# D5035-01.net
KiCad netlist of a schematic drawn in Altium Designer
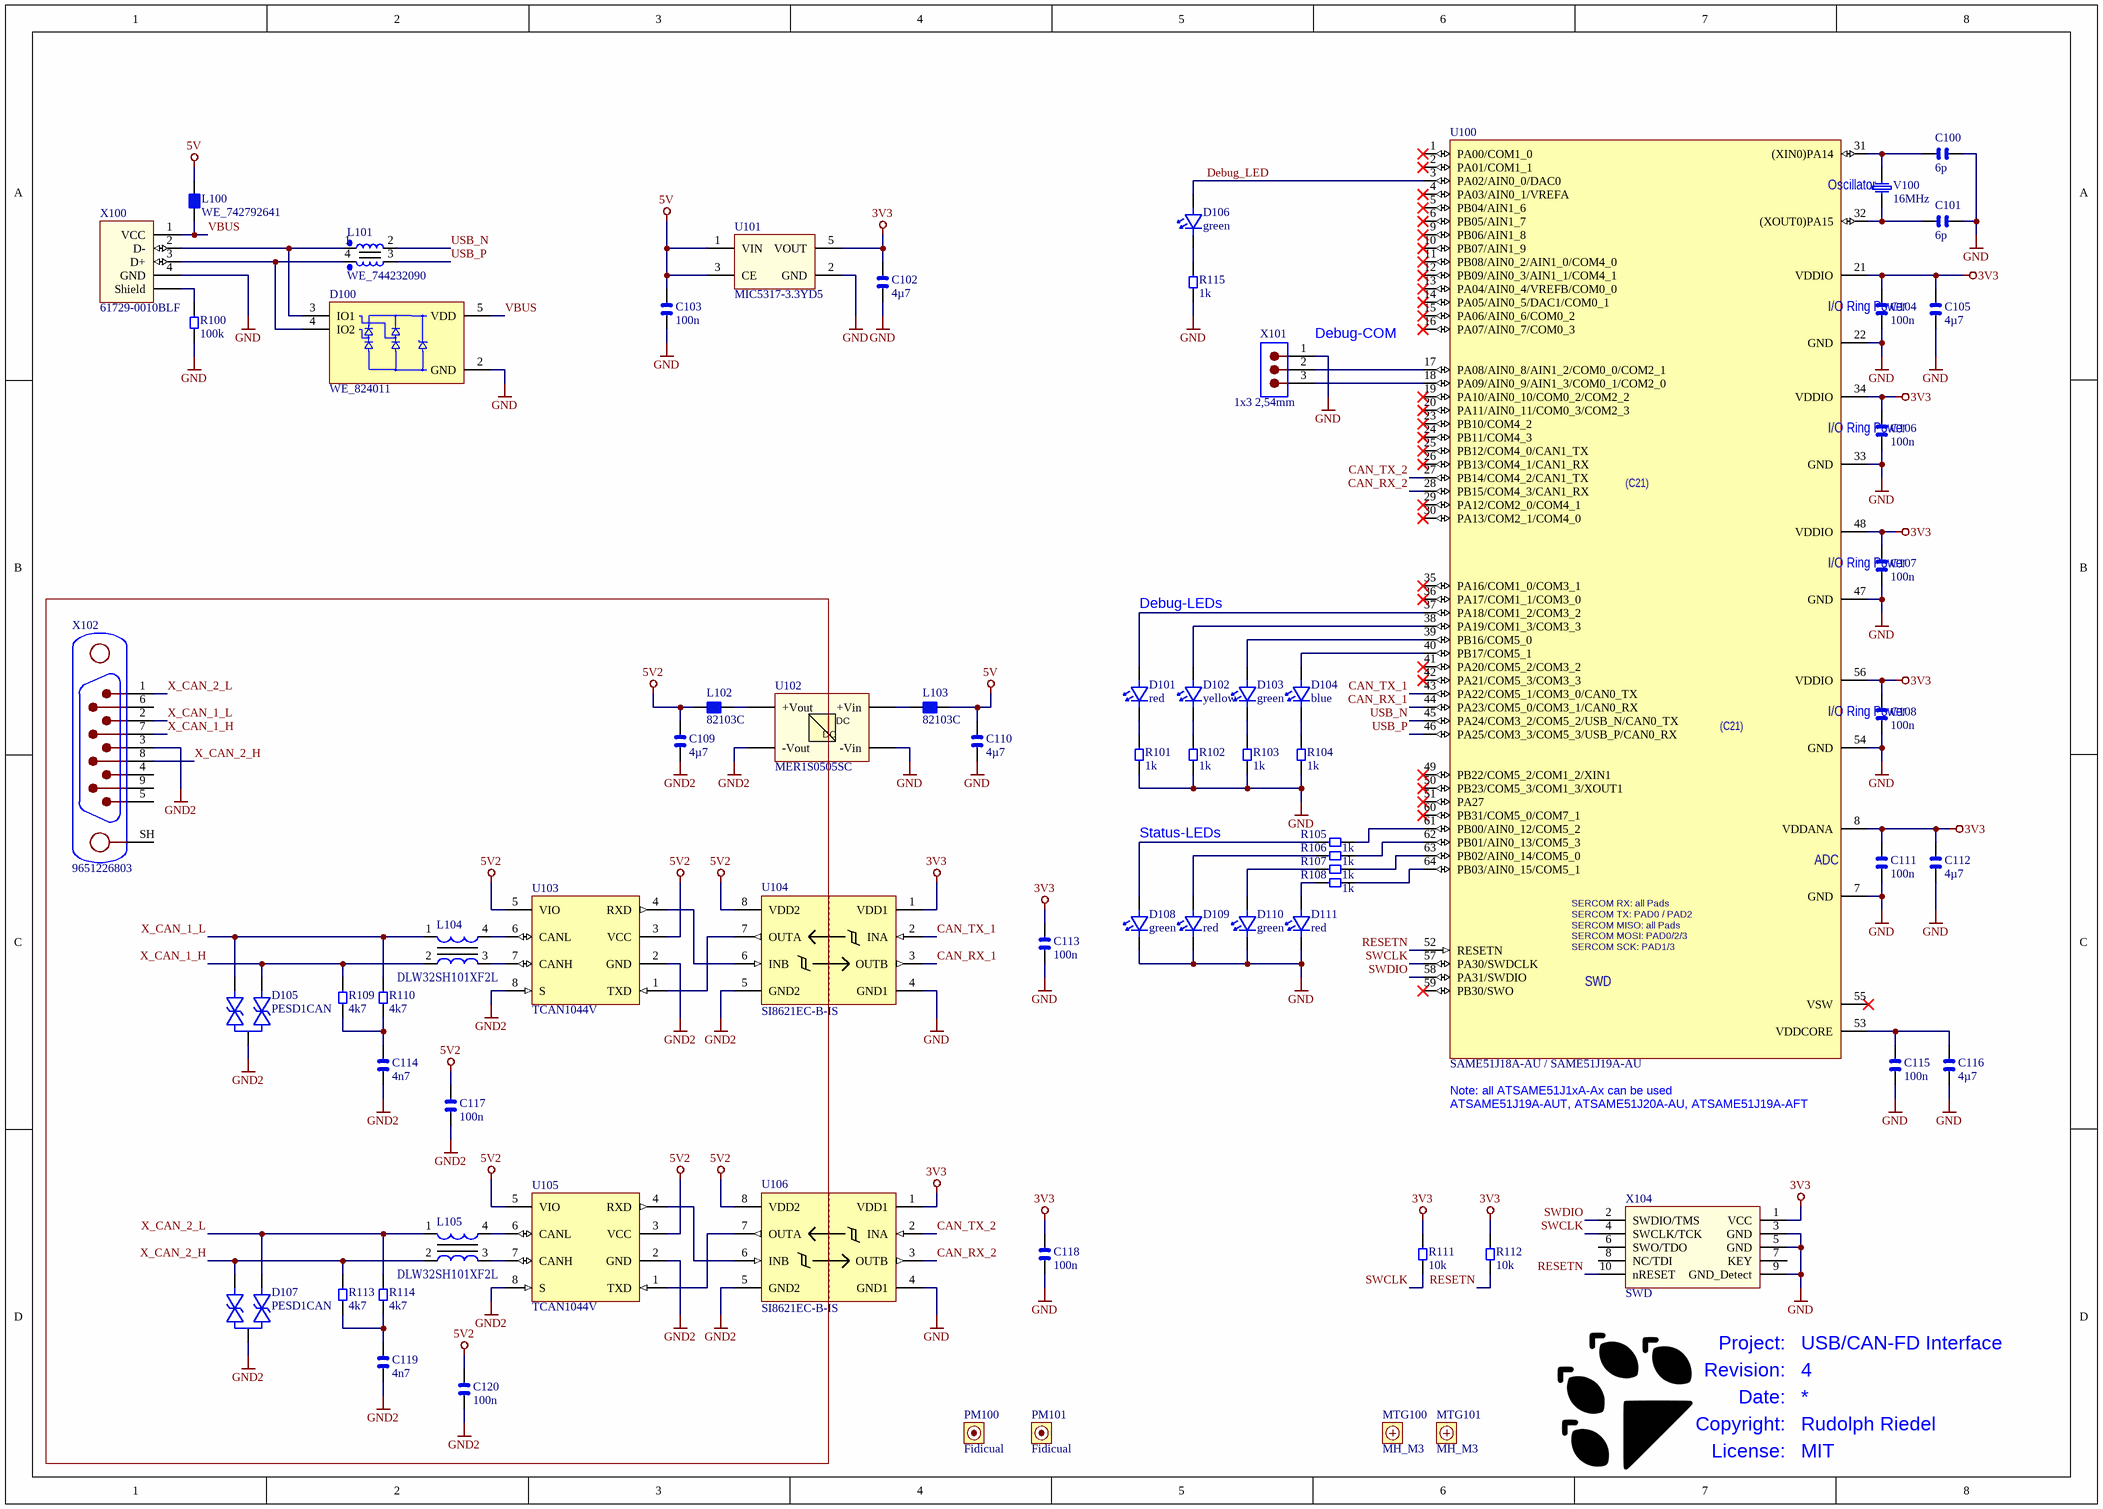
[diagram p0: D5035-01.SchDoc]

(export (version "E")
  (design (tool "Eeschema 10.0.6"))
  (components
    (comp (ref "C100")
      (value "6p")
      (footprint "CAPC1608X09L")
      (description "0603 Chip Capacitor")
      (fields (field (name "PART NUMBER") "CAPC_0603") (field (name "EDITOR") "rriedel"))
      (libsource (lib "HW-Labor_GF") (part "CAP_2_V2"))
    )
    (comp (ref "C101")
      (value "6p")
      (footprint "CAPC1608X09L")
      (description "0603 Chip Capacitor")
      (fields (field (name "PART NUMBER") "CAPC_0603") (field (name "EDITOR") "rriedel"))
      (libsource (lib "HW-Labor_GF") (part "CAP_2_V2"))
    )
    (comp (ref "C102")
      (value "4µ7")
      (footprint "CAPC2012X14L")
      (description "0805 Chip Capacitor")
      (fields (field (name "PART NUMBER") "CAPC_0805") (field (name "EDITOR") "rriedel"))
      (libsource (lib "HW-Labor_GF") (part "CAP_2_V2"))
    )
    (comp (ref "C103")
      (value "100n")
      (footprint "CAPC1608X09L")
      (description "0603 Chip Capacitor")
      (fields (field (name "PART NUMBER") "CAPC_0603") (field (name "EDITOR") "rriedel"))
      (libsource (lib "HW-Labor_GF") (part "CAP_2_V2"))
    )
    (comp (ref "C104")
      (value "100n")
      (footprint "CAPC1608X09L")
      (description "0603 Chip Capacitor")
      (fields (field (name "PART NUMBER") "CAPC_0603") (field (name "EDITOR") "rriedel"))
      (libsource (lib "HW-Labor_GF") (part "CAP_2_V2"))
    )
    (comp (ref "C105")
      (value "4µ7")
      (footprint "CAPC2012X14L")
      (description "0805 Chip Capacitor")
      (fields (field (name "PART NUMBER") "CAPC_0805") (field (name "EDITOR") "rriedel"))
      (libsource (lib "HW-Labor_GF") (part "CAP_2_V2"))
    )
    (comp (ref "C106")
      (value "100n")
      (footprint "CAPC1608X09L")
      (description "0603 Chip Capacitor")
      (fields (field (name "PART NUMBER") "CAPC_0603") (field (name "EDITOR") "rriedel"))
      (libsource (lib "HW-Labor_GF") (part "CAP_2_V2"))
    )
    (comp (ref "C107")
      (value "100n")
      (footprint "CAPC1608X09L")
      (description "0603 Chip Capacitor")
      (fields (field (name "PART NUMBER") "CAPC_0603") (field (name "EDITOR") "rriedel"))
      (libsource (lib "HW-Labor_GF") (part "CAP_2_V2"))
    )
    (comp (ref "C108")
      (value "100n")
      (footprint "CAPC1608X09L")
      (description "0603 Chip Capacitor")
      (fields (field (name "PART NUMBER") "CAPC_0603") (field (name "EDITOR") "rriedel"))
      (libsource (lib "HW-Labor_GF") (part "CAP_2_V2"))
    )
    (comp (ref "C109")
      (value "4µ7")
      (footprint "CAPC2012X14L")
      (description "0805 Chip Capacitor")
      (fields (field (name "PART NUMBER") "CAPC_0805") (field (name "EDITOR") "rriedel"))
      (libsource (lib "HW-Labor_GF") (part "CAP_2_V2"))
    )
    (comp (ref "C110")
      (value "4µ7")
      (footprint "CAPC2012X14L")
      (description "0805 Chip Capacitor")
      (fields (field (name "PART NUMBER") "CAPC_0805") (field (name "EDITOR") "rriedel"))
      (libsource (lib "HW-Labor_GF") (part "CAP_2_V2"))
    )
    (comp (ref "C111")
      (value "100n")
      (footprint "CAPC1608X09L")
      (description "0603 Chip Capacitor")
      (fields (field (name "PART NUMBER") "CAPC_0603") (field (name "EDITOR") "rriedel"))
      (libsource (lib "HW-Labor_GF") (part "CAP_2_V2"))
    )
    (comp (ref "C112")
      (value "4µ7")
      (footprint "CAPC2012X14L")
      (description "0805 Chip Capacitor")
      (fields (field (name "PART NUMBER") "CAPC_0805") (field (name "EDITOR") "rriedel"))
      (libsource (lib "HW-Labor_GF") (part "CAP_2_V2"))
    )
    (comp (ref "C113")
      (value "100n")
      (footprint "CAPC1608X09L")
      (description "0603 Chip Capacitor")
      (fields (field (name "PART NUMBER") "CAPC_0603") (field (name "EDITOR") "rriedel"))
      (libsource (lib "HW-Labor_GF") (part "CAP_2_V2"))
    )
    (comp (ref "C114")
      (value "4n7")
      (footprint "CAPC2012X14L")
      (description "0805 Chip Capacitor")
      (fields (field (name "PART NUMBER") "CAPC_0805") (field (name "EDITOR") "rriedel"))
      (libsource (lib "HW-Labor_GF") (part "CAP_2_V2"))
    )
    (comp (ref "C115")
      (value "100n")
      (footprint "CAPC1608X09L")
      (description "0603 Chip Capacitor")
      (fields (field (name "PART NUMBER") "CAPC_0603") (field (name "EDITOR") "rriedel"))
      (libsource (lib "HW-Labor_GF") (part "CAP_2_V2"))
    )
    (comp (ref "C116")
      (value "4µ7")
      (footprint "CAPC2012X14L")
      (description "0805 Chip Capacitor")
      (fields (field (name "PART NUMBER") "CAPC_0805") (field (name "EDITOR") "rriedel"))
      (libsource (lib "HW-Labor_GF") (part "CAP_2_V2"))
    )
    (comp (ref "C117")
      (value "100n")
      (footprint "CAPC1608X09L")
      (description "0603 Chip Capacitor")
      (fields (field (name "PART NUMBER") "CAPC_0603") (field (name "EDITOR") "rriedel"))
      (libsource (lib "HW-Labor_GF") (part "CAP_2_V2"))
    )
    (comp (ref "C118")
      (value "100n")
      (footprint "CAPC1608X09L")
      (description "0603 Chip Capacitor")
      (fields (field (name "PART NUMBER") "CAPC_0603") (field (name "EDITOR") "rriedel"))
      (libsource (lib "HW-Labor_GF") (part "CAP_2_V2"))
    )
    (comp (ref "C119")
      (value "4n7")
      (footprint "CAPC2012X14L")
      (description "0805 Chip Capacitor")
      (fields (field (name "PART NUMBER") "CAPC_0805") (field (name "EDITOR") "rriedel"))
      (libsource (lib "HW-Labor_GF") (part "CAP_2_V2"))
    )
    (comp (ref "C120")
      (value "100n")
      (footprint "CAPC1608X09L")
      (description "0603 Chip Capacitor")
      (fields (field (name "PART NUMBER") "CAPC_0603") (field (name "EDITOR") "rriedel"))
      (libsource (lib "HW-Labor_GF") (part "CAP_2_V2"))
    )
    (comp (ref "D100")
      (value "WE_824011")
      (footprint "SOT95P280X110-5N")
      (description "TVS Diode Array WE-TVS")
      (fields
        (field (name "MANUFACTURER") "Wuerth")
        (field (name "DISTRIBUTOR_1_PART_NUMBER") "732-4465-1-ND")
        (field (name "EDITOR") "rriedel")
      )
      (libsource (lib "HW-Labor_GF") (part "WE-824011"))
    )
    (comp (ref "D101")
      (value "red")
      (footprint "DIOC1608X06N_LED")
      (description "LED, 0603")
      (fields (field (name "PART NUMBER") "LED_0603") (field (name "EDITOR") "rriedel"))
      (libsource (lib "HW-Labor_GF") (part "LED_generic"))
    )
    (comp (ref "D102")
      (value "yellow")
      (footprint "DIOC1608X06N_LED")
      (description "LED, 0603")
      (fields (field (name "PART NUMBER") "LED_0603") (field (name "EDITOR") "rriedel"))
      (libsource (lib "HW-Labor_GF") (part "LED_generic"))
    )
    (comp (ref "D103")
      (value "green")
      (footprint "DIOC1608X06N_LED")
      (description "LED, 0603")
      (fields (field (name "PART NUMBER") "LED_0603") (field (name "EDITOR") "rriedel"))
      (libsource (lib "HW-Labor_GF") (part "LED_generic"))
    )
    (comp (ref "D104")
      (value "blue")
      (footprint "DIOC1608X06N_LED")
      (description "LED, 0603")
      (fields (field (name "PART NUMBER") "LED_0603") (field (name "EDITOR") "rriedel"))
      (libsource (lib "HW-Labor_GF") (part "LED_generic"))
    )
    (comp (ref "D105")
      (value "PESD1CAN")
      (footprint "SOT95P280X110-3N")
      (description "CAN bus ESD protection diode")
      (fields
        (field (name "MANUFACTURER") "Nexperia")
        (field (name "DISTRIBUTOR_1_PART_NUMBER") "1727-3817-1-ND")
        (field (name "EDITOR") "rriedel")
      )
      (libsource (lib "HW-Labor_GF") (part "PESD1CAN"))
    )
    (comp (ref "D106")
      (value "green")
      (footprint "DIOC1608X06N_LED")
      (description "LED, 0603")
      (fields (field (name "PART NUMBER") "LED_0603") (field (name "EDITOR") "rriedel"))
      (libsource (lib "HW-Labor_GF") (part "LED_generic"))
    )
    (comp (ref "D107")
      (value "PESD1CAN")
      (footprint "SOT95P280X110-3N")
      (description "CAN bus ESD protection diode")
      (fields
        (field (name "MANUFACTURER") "Nexperia")
        (field (name "DISTRIBUTOR_1_PART_NUMBER") "1727-3817-1-ND")
        (field (name "EDITOR") "rriedel")
      )
      (libsource (lib "HW-Labor_GF") (part "PESD1CAN"))
    )
    (comp (ref "D108")
      (value "green")
      (footprint "DIOC1608X06N_LED")
      (description "LED, 0603")
      (fields (field (name "PART NUMBER") "LED_0603") (field (name "EDITOR") "rriedel"))
      (libsource (lib "HW-Labor_GF") (part "LED_generic"))
    )
    (comp (ref "D109")
      (value "red")
      (footprint "DIOC1608X06N_LED")
      (description "LED, 0603")
      (fields (field (name "PART NUMBER") "LED_0603") (field (name "EDITOR") "rriedel"))
      (libsource (lib "HW-Labor_GF") (part "LED_generic"))
    )
    (comp (ref "D110")
      (value "green")
      (footprint "DIOC1608X06N_LED")
      (description "LED, 0603")
      (fields (field (name "PART NUMBER") "LED_0603") (field (name "EDITOR") "rriedel"))
      (libsource (lib "HW-Labor_GF") (part "LED_generic"))
    )
    (comp (ref "D111")
      (value "red")
      (footprint "DIOC1608X06N_LED")
      (description "LED, 0603")
      (fields (field (name "PART NUMBER") "LED_0603") (field (name "EDITOR") "rriedel"))
      (libsource (lib "HW-Labor_GF") (part "LED_generic"))
    )
    (comp (ref "L100")
      (value "WE_742792641")
      (footprint "INDC1608X06L")
      (description "SMT EMI suppression ferrite bead WE-CBF")
      (fields
        (field (name "MANUFACTURER") "Wuerth")
        (field (name "DISTRIBUTOR_1_PART_NUMBER") "732-1592-1-ND")
        (field (name "EDITOR") "rriedel")
      )
      (libsource (lib "HW-Labor_GF") (part "IND_2_V1"))
    )
    (comp (ref "L101")
      (value "WE_744232090")
      (footprint "WE_744232090")
      (description "SMD common mode noise suppressor WE-CNSW")
      (fields
        (field (name "MANUFACTURER") "Wuerth")
        (field (name "DISTRIBUTOR_1_PART_NUMBER") "732-1469-1-ND")
        (field (name "EDITOR") "rriedel")
      )
      (libsource (lib "HW-Labor_GF") (part "WE_744232090"))
    )
    (comp (ref "L102")
      (value "82103C")
      (footprint "Murata_8200C")
      (description "10µH, 0,5A, 400mR")
      (fields
        (field (name "MANUFACTURER") "Murata")
        (field (name "DISTRIBUTOR_1_PART_NUMBER") "811-2473-1-ND")
        (field (name "EDITOR") "rriedel")
      )
      (libsource (lib "HW-Labor_GF") (part "IND_2_V1"))
    )
    (comp (ref "L103")
      (value "82103C")
      (footprint "Murata_8200C")
      (description "10µH, 0,5A, 400mR")
      (fields
        (field (name "MANUFACTURER") "Murata")
        (field (name "DISTRIBUTOR_1_PART_NUMBER") "811-2473-1-ND")
        (field (name "EDITOR") "rriedel")
      )
      (libsource (lib "HW-Labor_GF") (part "IND_2_V1"))
    )
    (comp (ref "L104")
      (value "DLW32SH101XF2L‎")
      (footprint "ACT1210")
      (description "Common Mode Filter,  -50°C ... +150°C, AEC-Q200")
      (fields
        (field (name "PART NUMBER") "ACT1210-101-2P-TL00")
        (field (name "MANUFACTURER") "TDK")
        (field (name "EDITOR") "rriedel")
      )
      (libsource (lib "HW-Labor_GF") (part "CAN_DROSSEL"))
    )
    (comp (ref "L105")
      (value "DLW32SH101XF2L‎")
      (footprint "ACT1210")
      (description "Common Mode Filter,  -50°C ... +150°C, AEC-Q200")
      (fields
        (field (name "PART NUMBER") "ACT1210-101-2P-TL00")
        (field (name "MANUFACTURER") "TDK")
        (field (name "EDITOR") "rriedel")
      )
      (libsource (lib "HW-Labor_GF") (part "CAN_DROSSEL"))
    )
    (comp (ref "MTG100")
      (value "MH_M3")
      (footprint "HOLE_3_2MM")
      (description "Mounting-Hole for M3 screws")
      (fields (field (name "EDITOR") "rriedel"))
      (libsource (lib "HW-Labor_GF") (part "MTG_V1"))
    )
    (comp (ref "MTG101")
      (value "MH_M3")
      (footprint "HOLE_3_2MM")
      (description "Mounting-Hole for M3 screws")
      (fields (field (name "EDITOR") "rriedel"))
      (libsource (lib "HW-Labor_GF") (part "MTG_V1"))
    )
    (comp (ref "PM100")
      (value "Fidicual")
      (footprint "PM100")
      (fields (field (name "PART NUMBER") "PM100") (field (name "EDITOR") "rriedel"))
      (libsource (lib "HW-Labor_GF") (part "PM100"))
    )
    (comp (ref "PM101")
      (value "Fidicual")
      (footprint "PM100")
      (fields (field (name "PART NUMBER") "PM100") (field (name "EDITOR") "rriedel"))
      (libsource (lib "HW-Labor_GF") (part "PM100"))
    )
    (comp (ref "R100")
      (value "100k")
      (footprint "RESC2012X06L")
      (description "0805 Chip Resistor")
      (fields (field (name "PART NUMBER") "RESC_0805") (field (name "EDITOR") "rriedel"))
      (libsource (lib "HW-Labor_GF") (part "RES_2_V2"))
    )
    (comp (ref "R101")
      (value "1k")
      (footprint "RESC1608X06L")
      (description "0603 Chip Resistor")
      (fields (field (name "PART NUMBER") "RESC_0603") (field (name "EDITOR") "rriedel"))
      (libsource (lib "HW-Labor_GF") (part "RES_2_V2"))
    )
    (comp (ref "R102")
      (value "1k")
      (footprint "RESC1608X06L")
      (description "0603 Chip Resistor")
      (fields (field (name "PART NUMBER") "RESC_0603") (field (name "EDITOR") "rriedel"))
      (libsource (lib "HW-Labor_GF") (part "RES_2_V2"))
    )
    (comp (ref "R103")
      (value "1k")
      (footprint "RESC1608X06L")
      (description "0603 Chip Resistor")
      (fields (field (name "PART NUMBER") "RESC_0603") (field (name "EDITOR") "rriedel"))
      (libsource (lib "HW-Labor_GF") (part "RES_2_V2"))
    )
    (comp (ref "R104")
      (value "1k")
      (footprint "RESC1608X06L")
      (description "0603 Chip Resistor")
      (fields (field (name "PART NUMBER") "RESC_0603") (field (name "EDITOR") "rriedel"))
      (libsource (lib "HW-Labor_GF") (part "RES_2_V2"))
    )
    (comp (ref "R105")
      (value "1k")
      (footprint "RESC1608X06L")
      (description "0603 Chip Resistor")
      (fields (field (name "PART NUMBER") "RESC_0603") (field (name "EDITOR") "rriedel"))
      (libsource (lib "HW-Labor_GF") (part "RES_2_V2"))
    )
    (comp (ref "R106")
      (value "1k")
      (footprint "RESC1608X06L")
      (description "0603 Chip Resistor")
      (fields (field (name "PART NUMBER") "RESC_0603") (field (name "EDITOR") "rriedel"))
      (libsource (lib "HW-Labor_GF") (part "RES_2_V2"))
    )
    (comp (ref "R107")
      (value "1k")
      (footprint "RESC1608X06L")
      (description "0603 Chip Resistor")
      (fields (field (name "PART NUMBER") "RESC_0603") (field (name "EDITOR") "rriedel"))
      (libsource (lib "HW-Labor_GF") (part "RES_2_V2"))
    )
    (comp (ref "R108")
      (value "1k")
      (footprint "RESC1608X06L")
      (description "0603 Chip Resistor")
      (fields (field (name "PART NUMBER") "RESC_0603") (field (name "EDITOR") "rriedel"))
      (libsource (lib "HW-Labor_GF") (part "RES_2_V2"))
    )
    (comp (ref "R109")
      (value "4k7")
      (footprint "RESC2012X06L")
      (description "0805 Chip Resistor")
      (fields (field (name "PART NUMBER") "RESC_0805") (field (name "EDITOR") "rriedel"))
      (libsource (lib "HW-Labor_GF") (part "RES_2_V2"))
    )
    (comp (ref "R110")
      (value "4k7")
      (footprint "RESC2012X06L")
      (description "0805 Chip Resistor")
      (fields (field (name "PART NUMBER") "RESC_0805") (field (name "EDITOR") "rriedel"))
      (libsource (lib "HW-Labor_GF") (part "RES_2_V2"))
    )
    (comp (ref "R111")
      (value "10k")
      (footprint "RESC2012X06L")
      (description "0805 Chip Resistor")
      (fields (field (name "PART NUMBER") "RESC_0805") (field (name "EDITOR") "rriedel"))
      (libsource (lib "HW-Labor_GF") (part "RES_2_V2"))
    )
    (comp (ref "R112")
      (value "10k")
      (footprint "RESC2012X06L")
      (description "0805 Chip Resistor")
      (fields (field (name "PART NUMBER") "RESC_0805") (field (name "EDITOR") "rriedel"))
      (libsource (lib "HW-Labor_GF") (part "RES_2_V2"))
    )
    (comp (ref "R113")
      (value "4k7")
      (footprint "RESC2012X06L")
      (description "0805 Chip Resistor")
      (fields (field (name "PART NUMBER") "RESC_0805") (field (name "EDITOR") "rriedel"))
      (libsource (lib "HW-Labor_GF") (part "RES_2_V2"))
    )
    (comp (ref "R114")
      (value "4k7")
      (footprint "RESC2012X06L")
      (description "0805 Chip Resistor")
      (fields (field (name "PART NUMBER") "RESC_0805") (field (name "EDITOR") "rriedel"))
      (libsource (lib "HW-Labor_GF") (part "RES_2_V2"))
    )
    (comp (ref "R115")
      (value "1k")
      (footprint "RESC1608X06L")
      (description "0603 Chip Resistor")
      (fields (field (name "PART NUMBER") "RESC_0603") (field (name "EDITOR") "rriedel"))
      (libsource (lib "HW-Labor_GF") (part "RES_2_V2"))
    )
    (comp (ref "U100")
      (value "SAME51J18A-AU / SAME51J19A-AU")
      (footprint "TSQFP50P1200X1200X120-64N")
      (description "32-bit Microcontroller, 120MHz Cortex M4-F, 512k FLASH,  2x CAN-FD, -40…85°C")
      (fields
        (field (name "PART NUMBER") "SAME51J19A-AU")
        (field (name "MANUFACTURER") "Microchip")
        (field (name "EDITOR") "rriedel")
      )
      (libsource (lib "HW-Labor_GF") (part "SAME5xJxxA-AUx"))
    )
    (comp (ref "U101")
      (value "MIC5317-3.3YD5")
      (footprint "SOT95P280X110-5N")
      (description "100 mA LDO,  Vout= 3,3V, -40°C..125°C")
      (fields
        (field (name "PART NUMBER") "MIC5233-3.3")
        (field (name "MANUFACTURER") "Microchip")
        (field (name "EDITOR") "rriedel")
      )
      (libsource (lib "HW-Labor_GF") (part "LDO_SOT23-5"))
    )
    (comp (ref "U102")
      (value "MER1S0505SC")
      (footprint "MER1SxxxxC")
      (description "Isolated 1W Single Output DC-DC Converters 5V/5V 200mA")
      (fields
        (field (name "MANUFACTURER") "Murata")
        (field (name "DISTRIBUTOR_1_PART_NUMBER") "811-2124-5-ND‎")
        (field (name "EDITOR") "rriedel")
      )
      (libsource (lib "HW-Labor_GF") (part "MER1SxxxxC"))
    )
    (comp (ref "U103")
      (value "TCAN1044V")
      (footprint "SOT65P280X100-8N")
      (description "CAN-FD transceiver 8MBit, VIO Pin")
      (fields
        (field (name "MANUFACTURER") "TI")
        (field (name "DISTRIBUTOR_1_PART_NUMBER") "296-TCAN1044VDDFRCT-ND")
        (field (name "EDITOR") "rriedel")
      )
      (libsource (lib "HW-Labor_GF") (part "TJA1051T_3"))
    )
    (comp (ref "U104")
      (value "SI8621EC-B-IS")
      (footprint "SOIC127P600X175-8N")
      (description "Dual channel digital isolator, 150Mbit, 3,75kV")
      (fields
        (field (name "MANUFACTURER") "Silicon Labs")
        (field (name "DISTRIBUTOR_1_PART_NUMBER") "336-4776-1-ND")
        (field (name "EDITOR") "rriedel")
      )
      (libsource (lib "HW-Labor_GF") (part "SI8621"))
    )
    (comp (ref "U105")
      (value "TCAN1044V")
      (footprint "SOT65P280X100-8N")
      (description "CAN-FD transceiver 8MBit, VIO Pin")
      (fields
        (field (name "MANUFACTURER") "TI")
        (field (name "DISTRIBUTOR_1_PART_NUMBER") "296-TCAN1044VDDFRCT-ND")
        (field (name "EDITOR") "rriedel")
      )
      (libsource (lib "HW-Labor_GF") (part "TJA1051T_3"))
    )
    (comp (ref "U106")
      (value "SI8621EC-B-IS")
      (footprint "SOIC127P600X175-8N")
      (description "Dual channel digital isolator, 150Mbit, 3,75kV")
      (fields
        (field (name "MANUFACTURER") "Silicon Labs")
        (field (name "DISTRIBUTOR_1_PART_NUMBER") "336-4776-1-ND")
        (field (name "EDITOR") "rriedel")
      )
      (libsource (lib "HW-Labor_GF") (part "SI8621"))
    )
    (comp (ref "V100")
      (value "16MHz")
      (footprint "NX3225Gx")
      (description "16.000MHz Crystal SMD, 3.2x2.5mm, 8pF, 50ppm,  -40..+150°C")
      (fields
        (field (name "PART NUMBER") "NX3225GB-16.000000MHZ")
        (field (name "MANUFACTURER") "NDK")
        (field (name "EDITOR") "rriedel")
      )
      (libsource (lib "HW-Labor_GF") (part "XTAL_2_V1"))
    )
    (comp (ref "X100")
      (value "61729-0010BLF")
      (footprint "61729-xxxxxLF")
      (description "USB-B socket, THT")
      (fields
        (field (name "MANUFACTURER") "Amphenol")
        (field (name "DISTRIBUTOR_1_PART_NUMBER") "609-1039-ND")
        (field (name "EDITOR") "rriedel")
      )
      (libsource (lib "HW-Labor_GF") (part "USB"))
    )
    (comp (ref "X101")
      (value "1x3 2,54mm")
      (footprint "PINH_1x03_2_54mm")
      (description "Pin-Header 2,54 mm 3pins")
      (fields (field (name "PART NUMBER") "PINH_1x3_2_54") (field (name "EDITOR") "rriedel"))
      (libsource (lib "HW-Labor_GF") (part "CONM_1x3_V2"))
    )
    (comp (ref "X102")
      (value "9651226803")
      (footprint "09651226803")
      (description "D-Sub, 9 pin, male, right angle")
      (fields
        (field (name "MANUFACTURER") "Harting")
        (field (name "DISTRIBUTOR_1_PART_NUMBER") "2752007")
        (field (name "EDITOR") "rriedel")
      )
      (libsource (lib "HW-Labor_GF") (part "D_Sub_9_Male"))
    )
    (comp (ref "X104")
      (value "SWD")
      (footprint "FTSH-105-01-L-DV-K")
      (description "ARM Debug-Header 2x5 1,27 mm")
      (fields (field (name "EDITOR") "rriedel"))
      (libsource (lib "HW-Labor_GF") (part "SWD"))
    )
  )
  (nets
    (net (code "1") (name "/CAN_RX_1") (class "Default")
      (node (ref "U100") (pin "44") (pinfunction "PA23/COM5_0/COM3_1/CAN0_RX_44") (pintype "bidirectional"))
      (node (ref "U104") (pin "3") (pinfunction "OUTB_3") (pintype "output"))
    )
    (net (code "2") (name "/CAN_RX_2") (class "Default")
      (node (ref "U100") (pin "28") (pinfunction "PB15/COM4_3/CAN1_RX_28") (pintype "bidirectional"))
      (node (ref "U106") (pin "3") (pinfunction "OUTB_3") (pintype "output"))
    )
    (net (code "3") (name "/CAN_TX_1") (class "Default")
      (node (ref "U100") (pin "43") (pinfunction "PA22/COM5_1/COM3_0/CAN0_TX_43") (pintype "bidirectional"))
      (node (ref "U104") (pin "2") (pinfunction "INA_2") (pintype "input"))
    )
    (net (code "4") (name "/CAN_TX_2") (class "Default")
      (node (ref "U100") (pin "27") (pinfunction "PB14/COM4_2/CAN1_TX_27") (pintype "bidirectional"))
      (node (ref "U106") (pin "2") (pinfunction "INA_2") (pintype "input"))
    )
    (net (code "5") (name "/Debug_LED") (class "Default")
      (node (ref "D106") (pin "2") (pinfunction "2_2") (pintype "passive"))
      (node (ref "U100") (pin "3") (pinfunction "PA02/AIN0_0/DAC0_3") (pintype "bidirectional"))
    )
    (net (code "6") (name "/RESETN") (class "Default")
      (node (ref "R112") (pin "1") (pinfunction "1_1") (pintype "passive"))
      (node (ref "U100") (pin "52") (pinfunction "RESETN_52") (pintype "input"))
      (node (ref "X104") (pin "10") (pinfunction "nRESET_10") (pintype "passive"))
    )
    (net (code "7") (name "/SWCLK") (class "Default")
      (node (ref "R111") (pin "1") (pinfunction "1_1") (pintype "passive"))
      (node (ref "U100") (pin "57") (pinfunction "PA30/SWDCLK_57") (pintype "bidirectional"))
      (node (ref "X104") (pin "4") (pinfunction "SWCLK/TCK_4") (pintype "passive"))
    )
    (net (code "8") (name "/SWDIO") (class "Default")
      (node (ref "U100") (pin "58") (pinfunction "PA31/SWDIO_58") (pintype "bidirectional"))
      (node (ref "X104") (pin "2") (pinfunction "SWDIO/TMS_2") (pintype "passive"))
    )
    (net (code "9") (name "/USB_N") (class "Default")
      (node (ref "L101") (pin "2") (pinfunction "2_2") (pintype "passive"))
      (node (ref "U100") (pin "45") (pinfunction "PA24/COM3_2/COM5_2/USB_N/CAN0_TX_45") (pintype "bidirectional"))
    )
    (net (code "10") (name "/USB_P") (class "Default")
      (node (ref "L101") (pin "3") (pinfunction "3_3") (pintype "passive"))
      (node (ref "U100") (pin "46") (pinfunction "PA25/COM3_3/COM5_3/USB_P/CAN0_RX_46") (pintype "bidirectional"))
    )
    (net (code "11") (name "/VBUS") (class "Default")
      (node (ref "D100") (pin "5") (pinfunction "VDD_5") (pintype "passive"))
      (node (ref "L100") (pin "1") (pinfunction "1_1") (pintype "passive"))
      (node (ref "X100") (pin "1") (pinfunction "VCC_1") (pintype "power_in"))
    )
    (net (code "12") (name "/X_CAN_1_H") (class "Default")
      (node (ref "D105") (pin "2") (pinfunction "2_2") (pintype "passive"))
      (node (ref "L104") (pin "2") (pintype "passive"))
      (node (ref "R109") (pin "2") (pinfunction "2_2") (pintype "passive"))
      (node (ref "X102") (pin "7") (pinfunction "7_7") (pintype "passive"))
    )
    (net (code "13") (name "/X_CAN_1_L") (class "Default")
      (node (ref "D105") (pin "1") (pinfunction "1_1") (pintype "passive"))
      (node (ref "L104") (pin "1") (pintype "passive"))
      (node (ref "R110") (pin "2") (pinfunction "2_2") (pintype "passive"))
      (node (ref "X102") (pin "2") (pinfunction "2_2") (pintype "passive"))
    )
    (net (code "14") (name "/X_CAN_2_H") (class "Default")
      (node (ref "D107") (pin "1") (pinfunction "1_1") (pintype "passive"))
      (node (ref "L105") (pin "2") (pintype "passive"))
      (node (ref "R113") (pin "2") (pinfunction "2_2") (pintype "passive"))
      (node (ref "X102") (pin "8") (pinfunction "8_8") (pintype "passive"))
    )
    (net (code "15") (name "/X_CAN_2_L") (class "Default")
      (node (ref "D107") (pin "2") (pinfunction "2_2") (pintype "passive"))
      (node (ref "L105") (pin "1") (pintype "passive"))
      (node (ref "R114") (pin "2") (pinfunction "2_2") (pintype "passive"))
      (node (ref "X102") (pin "1") (pinfunction "1_1") (pintype "passive"))
    )
    (net (code "16") (name "3V3") (class "Default")
      (node (ref "C102") (pin "2") (pinfunction "2_2") (pintype "passive"))
      (node (ref "C104") (pin "2") (pinfunction "2_2") (pintype "passive"))
      (node (ref "C105") (pin "2") (pinfunction "2_2") (pintype "passive"))
      (node (ref "C106") (pin "2") (pinfunction "2_2") (pintype "passive"))
      (node (ref "C107") (pin "2") (pinfunction "2_2") (pintype "passive"))
      (node (ref "C108") (pin "2") (pinfunction "2_2") (pintype "passive"))
      (node (ref "C111") (pin "2") (pinfunction "2_2") (pintype "passive"))
      (node (ref "C112") (pin "2") (pinfunction "2_2") (pintype "passive"))
      (node (ref "C113") (pin "2") (pinfunction "2_2") (pintype "passive"))
      (node (ref "C118") (pin "2") (pinfunction "2_2") (pintype "passive"))
      (node (ref "R111") (pin "2") (pinfunction "2_2") (pintype "passive"))
      (node (ref "R112") (pin "2") (pinfunction "2_2") (pintype "passive"))
      (node (ref "U100") (pin "21") (pinfunction "VDDIO_21") (pintype "power_in"))
      (node (ref "U100") (pin "34") (pinfunction "VDDIO_34") (pintype "power_in"))
      (node (ref "U100") (pin "48") (pinfunction "VDDIO_48") (pintype "power_in"))
      (node (ref "U100") (pin "56") (pinfunction "VDDIO_56") (pintype "power_in"))
      (node (ref "U100") (pin "8") (pinfunction "VDDANA_8") (pintype "power_in"))
      (node (ref "U101") (pin "5") (pinfunction "VOUT_5") (pintype "passive"))
      (node (ref "U104") (pin "1") (pinfunction "VDD1_1") (pintype "power_in"))
      (node (ref "U106") (pin "1") (pinfunction "VDD1_1") (pintype "power_in"))
      (node (ref "X104") (pin "1") (pinfunction "VCC_1") (pintype "power_in"))
    )
    (net (code "17") (name "5V") (class "Default")
      (node (ref "C103") (pin "2") (pinfunction "2_2") (pintype "passive"))
      (node (ref "C110") (pin "2") (pinfunction "2_2") (pintype "passive"))
      (node (ref "L100") (pin "2") (pinfunction "2_2") (pintype "passive"))
      (node (ref "L103") (pin "1") (pinfunction "1_1") (pintype "passive"))
      (node (ref "U101") (pin "1") (pinfunction "VIN_1") (pintype "passive"))
      (node (ref "U101") (pin "3") (pinfunction "CE_3") (pintype "passive"))
    )
    (net (code "18") (name "5V2") (class "Default")
      (node (ref "C109") (pin "2") (pinfunction "2_2") (pintype "passive"))
      (node (ref "C117") (pin "2") (pinfunction "2_2") (pintype "passive"))
      (node (ref "C120") (pin "2") (pinfunction "2_2") (pintype "passive"))
      (node (ref "L102") (pin "2") (pinfunction "2_2") (pintype "passive"))
      (node (ref "U103") (pin "3") (pinfunction "VCC_3") (pintype "power_in"))
      (node (ref "U103") (pin "5") (pinfunction "VIO_5") (pintype "power_in"))
      (node (ref "U104") (pin "8") (pinfunction "VDD2_8") (pintype "power_in"))
      (node (ref "U105") (pin "3") (pinfunction "VCC_3") (pintype "power_in"))
      (node (ref "U105") (pin "5") (pinfunction "VIO_5") (pintype "power_in"))
      (node (ref "U106") (pin "8") (pinfunction "VDD2_8") (pintype "power_in"))
    )
    (net (code "19") (name "GND") (class "Default")
      (node (ref "C100") (pin "2") (pinfunction "2_2") (pintype "passive"))
      (node (ref "C101") (pin "2") (pinfunction "2_2") (pintype "passive"))
      (node (ref "C102") (pin "1") (pinfunction "1_1") (pintype "passive"))
      (node (ref "C103") (pin "1") (pinfunction "1_1") (pintype "passive"))
      (node (ref "C104") (pin "1") (pinfunction "1_1") (pintype "passive"))
      (node (ref "C105") (pin "1") (pinfunction "1_1") (pintype "passive"))
      (node (ref "C106") (pin "1") (pinfunction "1_1") (pintype "passive"))
      (node (ref "C107") (pin "1") (pinfunction "1_1") (pintype "passive"))
      (node (ref "C108") (pin "1") (pinfunction "1_1") (pintype "passive"))
      (node (ref "C110") (pin "1") (pinfunction "1_1") (pintype "passive"))
      (node (ref "C111") (pin "1") (pinfunction "1_1") (pintype "passive"))
      (node (ref "C112") (pin "1") (pinfunction "1_1") (pintype "passive"))
      (node (ref "C113") (pin "1") (pinfunction "1_1") (pintype "passive"))
      (node (ref "C115") (pin "1") (pinfunction "1_1") (pintype "passive"))
      (node (ref "C116") (pin "1") (pinfunction "1_1") (pintype "passive"))
      (node (ref "C118") (pin "1") (pinfunction "1_1") (pintype "passive"))
      (node (ref "D100") (pin "2") (pinfunction "GND_2") (pintype "passive"))
      (node (ref "D108") (pin "1") (pinfunction "1_1") (pintype "passive"))
      (node (ref "D109") (pin "1") (pinfunction "1_1") (pintype "passive"))
      (node (ref "D110") (pin "1") (pinfunction "1_1") (pintype "passive"))
      (node (ref "D111") (pin "1") (pinfunction "1_1") (pintype "passive"))
      (node (ref "R100") (pin "1") (pinfunction "1_1") (pintype "passive"))
      (node (ref "R101") (pin "1") (pinfunction "1_1") (pintype "passive"))
      (node (ref "R102") (pin "1") (pinfunction "1_1") (pintype "passive"))
      (node (ref "R103") (pin "1") (pinfunction "1_1") (pintype "passive"))
      (node (ref "R104") (pin "1") (pinfunction "1_1") (pintype "passive"))
      (node (ref "R115") (pin "1") (pinfunction "1_1") (pintype "passive"))
      (node (ref "U100") (pin "22") (pinfunction "GND_22") (pintype "power_in"))
      (node (ref "U100") (pin "33") (pinfunction "GND_33") (pintype "power_in"))
      (node (ref "U100") (pin "47") (pinfunction "GND_47") (pintype "power_in"))
      (node (ref "U100") (pin "54") (pinfunction "GND_54") (pintype "power_in"))
      (node (ref "U100") (pin "7") (pinfunction "GND_7") (pintype "power_in"))
      (node (ref "U101") (pin "2") (pinfunction "GND_2") (pintype "passive"))
      (node (ref "U102") (pin "2") (pinfunction "-Vin_2") (pintype "power_in"))
      (node (ref "U104") (pin "4") (pinfunction "GND1_4") (pintype "power_in"))
      (node (ref "U106") (pin "4") (pinfunction "GND1_4") (pintype "power_in"))
      (node (ref "X100") (pin "4") (pinfunction "GND_4") (pintype "power_in"))
      (node (ref "X101") (pin "1") (pinfunction "1_1") (pintype "passive"))
      (node (ref "X104") (pin "3") (pinfunction "GND_3") (pintype "power_in"))
      (node (ref "X104") (pin "5") (pinfunction "GND_5") (pintype "power_in"))
      (node (ref "X104") (pin "9") (pinfunction "GND_Detect_9") (pintype "power_in"))
    )
    (net (code "20") (name "GND2") (class "Default")
      (node (ref "C109") (pin "1") (pinfunction "1_1") (pintype "passive"))
      (node (ref "C114") (pin "1") (pinfunction "1_1") (pintype "passive"))
      (node (ref "C117") (pin "1") (pinfunction "1_1") (pintype "passive"))
      (node (ref "C119") (pin "1") (pinfunction "1_1") (pintype "passive"))
      (node (ref "C120") (pin "1") (pinfunction "1_1") (pintype "passive"))
      (node (ref "D105") (pin "3") (pinfunction "3_3") (pintype "passive"))
      (node (ref "D107") (pin "3") (pinfunction "3_3") (pintype "passive"))
      (node (ref "U102") (pin "4") (pinfunction "-Vout_4") (pintype "power_in"))
      (node (ref "U103") (pin "2") (pinfunction "GND_2") (pintype "power_in"))
      (node (ref "U103") (pin "8") (pinfunction "S_8") (pintype "input"))
      (node (ref "U104") (pin "5") (pinfunction "GND2_5") (pintype "power_in"))
      (node (ref "U105") (pin "2") (pinfunction "GND_2") (pintype "power_in"))
      (node (ref "U105") (pin "8") (pinfunction "S_8") (pintype "input"))
      (node (ref "U106") (pin "5") (pinfunction "GND2_5") (pintype "power_in"))
      (node (ref "X102") (pin "3") (pinfunction "3_3") (pintype "passive"))
    )
    (net (code "21") (name "Net-(C114-Pad2)") (class "Default")
      (node (ref "C114") (pin "2") (pinfunction "2_2") (pintype "passive"))
      (node (ref "R109") (pin "1") (pinfunction "1_1") (pintype "passive"))
      (node (ref "R110") (pin "1") (pinfunction "1_1") (pintype "passive"))
    )
    (net (code "22") (name "Net-(C119-Pad2)") (class "Default")
      (node (ref "C119") (pin "2") (pinfunction "2_2") (pintype "passive"))
      (node (ref "R113") (pin "1") (pinfunction "1_1") (pintype "passive"))
      (node (ref "R114") (pin "1") (pinfunction "1_1") (pintype "passive"))
    )
    (net (code "23") (name "Net-(D100-IO1)") (class "Default")
      (node (ref "D100") (pin "3") (pinfunction "IO1_3") (pintype "passive"))
      (node (ref "L101") (pin "1") (pinfunction "1_1") (pintype "passive"))
      (node (ref "X100") (pin "2") (pinfunction "D-_2") (pintype "bidirectional"))
    )
    (net (code "24") (name "Net-(D100-IO2)") (class "Default")
      (node (ref "D100") (pin "4") (pinfunction "IO2_4") (pintype "passive"))
      (node (ref "L101") (pin "4") (pinfunction "4_4") (pintype "passive"))
      (node (ref "X100") (pin "3") (pinfunction "D+_3") (pintype "bidirectional"))
    )
    (net (code "25") (name "Net-(D101-Pad1)") (class "Default")
      (node (ref "D101") (pin "1") (pinfunction "1_1") (pintype "passive"))
      (node (ref "R101") (pin "2") (pinfunction "2_2") (pintype "passive"))
    )
    (net (code "26") (name "Net-(D102-Pad1)") (class "Default")
      (node (ref "D102") (pin "1") (pinfunction "1_1") (pintype "passive"))
      (node (ref "R102") (pin "2") (pinfunction "2_2") (pintype "passive"))
    )
    (net (code "27") (name "Net-(D103-Pad1)") (class "Default")
      (node (ref "D103") (pin "1") (pinfunction "1_1") (pintype "passive"))
      (node (ref "R103") (pin "2") (pinfunction "2_2") (pintype "passive"))
    )
    (net (code "28") (name "Net-(D104-Pad1)") (class "Default")
      (node (ref "D104") (pin "1") (pinfunction "1_1") (pintype "passive"))
      (node (ref "R104") (pin "2") (pinfunction "2_2") (pintype "passive"))
    )
    (net (code "29") (name "Net-(D106-Pad1)") (class "Default")
      (node (ref "D106") (pin "1") (pinfunction "1_1") (pintype "passive"))
      (node (ref "R115") (pin "2") (pinfunction "2_2") (pintype "passive"))
    )
    (net (code "30") (name "Net-(D108-Pad2)") (class "Default")
      (node (ref "D108") (pin "2") (pinfunction "2_2") (pintype "passive"))
      (node (ref "R105") (pin "1") (pinfunction "1_1") (pintype "passive"))
    )
    (net (code "31") (name "Net-(D109-Pad2)") (class "Default")
      (node (ref "D109") (pin "2") (pinfunction "2_2") (pintype "passive"))
      (node (ref "R106") (pin "1") (pinfunction "1_1") (pintype "passive"))
    )
    (net (code "32") (name "Net-(D110-Pad2)") (class "Default")
      (node (ref "D110") (pin "2") (pinfunction "2_2") (pintype "passive"))
      (node (ref "R107") (pin "1") (pinfunction "1_1") (pintype "passive"))
    )
    (net (code "33") (name "Net-(D111-Pad2)") (class "Default")
      (node (ref "D111") (pin "2") (pinfunction "2_2") (pintype "passive"))
      (node (ref "R108") (pin "1") (pinfunction "1_1") (pintype "passive"))
    )
    (net (code "34") (name "Net-(U100-(XIN0)PA14)") (class "Default")
      (node (ref "C100") (pin "1") (pinfunction "1_1") (pintype "passive"))
      (node (ref "U100") (pin "31") (pinfunction "(XIN0)PA14_31") (pintype "bidirectional"))
      (node (ref "V100") (pin "2") (pinfunction "2_2") (pintype "passive"))
    )
    (net (code "35") (name "Net-(U100-(XOUT0)PA15)") (class "Default")
      (node (ref "C101") (pin "1") (pinfunction "1_1") (pintype "passive"))
      (node (ref "U100") (pin "32") (pinfunction "(XOUT0)PA15_32") (pintype "bidirectional"))
      (node (ref "V100") (pin "1") (pinfunction "1_1") (pintype "passive"))
    )
    (net (code "36") (name "Net-(U100-PA08{slash}AIN0_8{slash}AIN1_2{slash}COM0_0{slash}COM2_1)") (class "Default")
      (node (ref "U100") (pin "17") (pinfunction "PA08/AIN0_8/AIN1_2/COM0_0/COM2_1_17") (pintype "bidirectional"))
      (node (ref "X101") (pin "2") (pinfunction "2_2") (pintype "passive"))
    )
    (net (code "37") (name "Net-(U100-PA09{slash}AIN0_9{slash}AIN1_3{slash}COM0_1{slash}COM2_0)") (class "Default")
      (node (ref "U100") (pin "18") (pinfunction "PA09/AIN0_9/AIN1_3/COM0_1/COM2_0_18") (pintype "bidirectional"))
      (node (ref "X101") (pin "3") (pinfunction "3_3") (pintype "passive"))
    )
    (net (code "38") (name "Net-(U100-PA18{slash}COM1_2{slash}COM3_2)") (class "Default")
      (node (ref "D101") (pin "2") (pinfunction "2_2") (pintype "passive"))
      (node (ref "U100") (pin "37") (pinfunction "PA18/COM1_2/COM3_2_37") (pintype "bidirectional"))
    )
    (net (code "39") (name "Net-(U100-PA19{slash}COM1_3{slash}COM3_3)") (class "Default")
      (node (ref "D102") (pin "2") (pinfunction "2_2") (pintype "passive"))
      (node (ref "U100") (pin "38") (pinfunction "PA19/COM1_3/COM3_3_38") (pintype "bidirectional"))
    )
    (net (code "40") (name "Net-(U100-PB00{slash}AIN0_12{slash}COM5_2)") (class "Default")
      (node (ref "R105") (pin "2") (pinfunction "2_2") (pintype "passive"))
      (node (ref "U100") (pin "61") (pinfunction "PB00/AIN0_12/COM5_2_61") (pintype "bidirectional"))
    )
    (net (code "41") (name "Net-(U100-PB01{slash}AIN0_13{slash}COM5_3)") (class "Default")
      (node (ref "R106") (pin "2") (pinfunction "2_2") (pintype "passive"))
      (node (ref "U100") (pin "62") (pinfunction "PB01/AIN0_13/COM5_3_62") (pintype "bidirectional"))
    )
    (net (code "42") (name "Net-(U100-PB02{slash}AIN0_14{slash}COM5_0)") (class "Default")
      (node (ref "R107") (pin "2") (pinfunction "2_2") (pintype "passive"))
      (node (ref "U100") (pin "63") (pinfunction "PB02/AIN0_14/COM5_0_63") (pintype "bidirectional"))
    )
    (net (code "43") (name "Net-(U100-PB03{slash}AIN0_15{slash}COM5_1)") (class "Default")
      (node (ref "R108") (pin "2") (pinfunction "2_2") (pintype "passive"))
      (node (ref "U100") (pin "64") (pinfunction "PB03/AIN0_15/COM5_1_64") (pintype "bidirectional"))
    )
    (net (code "44") (name "Net-(U100-PB16{slash}COM5_0)") (class "Default")
      (node (ref "D103") (pin "2") (pinfunction "2_2") (pintype "passive"))
      (node (ref "U100") (pin "39") (pinfunction "PB16/COM5_0_39") (pintype "bidirectional"))
    )
    (net (code "45") (name "Net-(U100-PB17{slash}COM5_1)") (class "Default")
      (node (ref "D104") (pin "2") (pinfunction "2_2") (pintype "passive"))
      (node (ref "U100") (pin "40") (pinfunction "PB17/COM5_1_40") (pintype "bidirectional"))
    )
    (net (code "46") (name "Net-(U100-VDDCORE)") (class "Default")
      (node (ref "C115") (pin "2") (pinfunction "2_2") (pintype "passive"))
      (node (ref "C116") (pin "2") (pinfunction "2_2") (pintype "passive"))
      (node (ref "U100") (pin "53") (pinfunction "VDDCORE_53") (pintype "passive"))
    )
    (net (code "47") (name "Net-(U102-+Vin)") (class "Default")
      (node (ref "L103") (pin "2") (pinfunction "2_2") (pintype "passive"))
      (node (ref "U102") (pin "1") (pinfunction "+Vin_1") (pintype "power_in"))
    )
    (net (code "48") (name "Net-(U102-+Vout)") (class "Default")
      (node (ref "L102") (pin "1") (pinfunction "1_1") (pintype "passive"))
      (node (ref "U102") (pin "6") (pinfunction "+Vout_6") (pintype "power_in"))
    )
    (net (code "49") (name "Net-(U103-CANH)") (class "Default")
      (node (ref "L104") (pin "3") (pintype "passive"))
      (node (ref "U103") (pin "7") (pinfunction "CANH_7") (pintype "bidirectional"))
    )
    (net (code "50") (name "Net-(U103-CANL)") (class "Default")
      (node (ref "L104") (pin "4") (pintype "passive"))
      (node (ref "U103") (pin "6") (pinfunction "CANL_6") (pintype "bidirectional"))
    )
    (net (code "51") (name "Net-(U103-RXD)") (class "Default")
      (node (ref "U103") (pin "4") (pinfunction "RXD_4") (pintype "output"))
      (node (ref "U104") (pin "6") (pinfunction "INB_6") (pintype "input"))
    )
    (net (code "52") (name "Net-(U103-TXD)") (class "Default")
      (node (ref "U103") (pin "1") (pinfunction "TXD_1") (pintype "input"))
      (node (ref "U104") (pin "7") (pinfunction "OUTA_7") (pintype "output"))
    )
    (net (code "53") (name "Net-(U105-CANH)") (class "Default")
      (node (ref "L105") (pin "3") (pintype "passive"))
      (node (ref "U105") (pin "7") (pinfunction "CANH_7") (pintype "bidirectional"))
    )
    (net (code "54") (name "Net-(U105-CANL)") (class "Default")
      (node (ref "L105") (pin "4") (pintype "passive"))
      (node (ref "U105") (pin "6") (pinfunction "CANL_6") (pintype "bidirectional"))
    )
    (net (code "55") (name "Net-(U105-RXD)") (class "Default")
      (node (ref "U105") (pin "4") (pinfunction "RXD_4") (pintype "output"))
      (node (ref "U106") (pin "6") (pinfunction "INB_6") (pintype "input"))
    )
    (net (code "56") (name "Net-(U105-TXD)") (class "Default")
      (node (ref "U105") (pin "1") (pinfunction "TXD_1") (pintype "input"))
      (node (ref "U106") (pin "7") (pinfunction "OUTA_7") (pintype "output"))
    )
    (net (code "57") (name "Net-(X100-Shield)") (class "Default")
      (node (ref "R100") (pin "2") (pinfunction "2_2") (pintype "passive"))
      (node (ref "X100") (pin "Shell") (pinfunction "Shield_Shell") (pintype "passive"))
    )
    (net (code "58") (name "unconnected-(U100-PA00{slash}COM1_0-Pad1)") (class "Default")
      (node (ref "U100") (pin "1") (pinfunction "PA00/COM1_0_1") (pintype "bidirectional+no_connect"))
    )
    (net (code "59") (name "unconnected-(U100-PA01{slash}COM1_1-Pad2)") (class "Default")
      (node (ref "U100") (pin "2") (pinfunction "PA01/COM1_1_2") (pintype "bidirectional+no_connect"))
    )
    (net (code "60") (name "unconnected-(U100-PA03{slash}AIN0_1{slash}VREFA-Pad4)") (class "Default")
      (node (ref "U100") (pin "4") (pinfunction "PA03/AIN0_1/VREFA_4") (pintype "bidirectional+no_connect"))
    )
    (net (code "61") (name "unconnected-(U100-PA04{slash}AIN0_4{slash}VREFB{slash}COM0_0-Pad13)") (class "Default")
      (node (ref "U100") (pin "13") (pinfunction "PA04/AIN0_4/VREFB/COM0_0_13") (pintype "bidirectional+no_connect"))
    )
    (net (code "62") (name "unconnected-(U100-PA05{slash}AIN0_5{slash}DAC1{slash}COM0_1-Pad14)") (class "Default")
      (node (ref "U100") (pin "14") (pinfunction "PA05/AIN0_5/DAC1/COM0_1_14") (pintype "bidirectional+no_connect"))
    )
    (net (code "63") (name "unconnected-(U100-PA06{slash}AIN0_6{slash}COM0_2-Pad15)") (class "Default")
      (node (ref "U100") (pin "15") (pinfunction "PA06/AIN0_6/COM0_2_15") (pintype "bidirectional+no_connect"))
    )
    (net (code "64") (name "unconnected-(U100-PA07{slash}AIN0_7{slash}COM0_3-Pad16)") (class "Default")
      (node (ref "U100") (pin "16") (pinfunction "PA07/AIN0_7/COM0_3_16") (pintype "bidirectional+no_connect"))
    )
    (net (code "65") (name "unconnected-(U100-PA10{slash}AIN0_10{slash}COM0_2{slash}COM2_2-Pad19)") (class "Default")
      (node (ref "U100") (pin "19") (pinfunction "PA10/AIN0_10/COM0_2/COM2_2_19") (pintype "bidirectional+no_connect"))
    )
    (net (code "66") (name "unconnected-(U100-PA11{slash}AIN0_11{slash}COM0_3{slash}COM2_3-Pad20)") (class "Default")
      (node (ref "U100") (pin "20") (pinfunction "PA11/AIN0_11/COM0_3/COM2_3_20") (pintype "bidirectional+no_connect"))
    )
    (net (code "67") (name "unconnected-(U100-PA12{slash}COM2_0{slash}COM4_1-Pad29)") (class "Default")
      (node (ref "U100") (pin "29") (pinfunction "PA12/COM2_0/COM4_1_29") (pintype "bidirectional+no_connect"))
    )
    (net (code "68") (name "unconnected-(U100-PA13{slash}COM2_1{slash}COM4_0-Pad30)") (class "Default")
      (node (ref "U100") (pin "30") (pinfunction "PA13/COM2_1/COM4_0_30") (pintype "bidirectional+no_connect"))
    )
    (net (code "69") (name "unconnected-(U100-PA16{slash}COM1_0{slash}COM3_1-Pad35)") (class "Default")
      (node (ref "U100") (pin "35") (pinfunction "PA16/COM1_0/COM3_1_35") (pintype "bidirectional+no_connect"))
    )
    (net (code "70") (name "unconnected-(U100-PA17{slash}COM1_1{slash}COM3_0-Pad36)") (class "Default")
      (node (ref "U100") (pin "36") (pinfunction "PA17/COM1_1/COM3_0_36") (pintype "bidirectional+no_connect"))
    )
    (net (code "71") (name "unconnected-(U100-PA20{slash}COM5_2{slash}COM3_2-Pad41)") (class "Default")
      (node (ref "U100") (pin "41") (pinfunction "PA20/COM5_2/COM3_2_41") (pintype "bidirectional+no_connect"))
    )
    (net (code "72") (name "unconnected-(U100-PA21{slash}COM5_3{slash}COM3_3-Pad42)") (class "Default")
      (node (ref "U100") (pin "42") (pinfunction "PA21/COM5_3/COM3_3_42") (pintype "bidirectional+no_connect"))
    )
    (net (code "73") (name "unconnected-(U100-PA27-Pad51)") (class "Default")
      (node (ref "U100") (pin "51") (pinfunction "PA27_51") (pintype "bidirectional+no_connect"))
    )
    (net (code "74") (name "unconnected-(U100-PB04{slash}AIN1_6-Pad5)") (class "Default")
      (node (ref "U100") (pin "5") (pinfunction "PB04/AIN1_6_5") (pintype "bidirectional+no_connect"))
    )
    (net (code "75") (name "unconnected-(U100-PB05{slash}AIN1_7-Pad6)") (class "Default")
      (node (ref "U100") (pin "6") (pinfunction "PB05/AIN1_7_6") (pintype "bidirectional+no_connect"))
    )
    (net (code "76") (name "unconnected-(U100-PB06{slash}AIN1_8-Pad9)") (class "Default")
      (node (ref "U100") (pin "9") (pinfunction "PB06/AIN1_8_9") (pintype "bidirectional+no_connect"))
    )
    (net (code "77") (name "unconnected-(U100-PB07{slash}AIN1_9-Pad10)") (class "Default")
      (node (ref "U100") (pin "10") (pinfunction "PB07/AIN1_9_10") (pintype "bidirectional+no_connect"))
    )
    (net (code "78") (name "unconnected-(U100-PB08{slash}AIN0_2{slash}AIN1_0{slash}COM4_0-Pad11)") (class "Default")
      (node (ref "U100") (pin "11") (pinfunction "PB08/AIN0_2/AIN1_0/COM4_0_11") (pintype "bidirectional+no_connect"))
    )
    (net (code "79") (name "unconnected-(U100-PB09{slash}AIN0_3{slash}AIN1_1{slash}COM4_1-Pad12)") (class "Default")
      (node (ref "U100") (pin "12") (pinfunction "PB09/AIN0_3/AIN1_1/COM4_1_12") (pintype "bidirectional+no_connect"))
    )
    (net (code "80") (name "unconnected-(U100-PB10{slash}COM4_2-Pad23)") (class "Default")
      (node (ref "U100") (pin "23") (pinfunction "PB10/COM4_2_23") (pintype "bidirectional+no_connect"))
    )
    (net (code "81") (name "unconnected-(U100-PB11{slash}COM4_3-Pad24)") (class "Default")
      (node (ref "U100") (pin "24") (pinfunction "PB11/COM4_3_24") (pintype "bidirectional+no_connect"))
    )
    (net (code "82") (name "unconnected-(U100-PB12{slash}COM4_0{slash}CAN1_TX-Pad25)") (class "Default")
      (node (ref "U100") (pin "25") (pinfunction "PB12/COM4_0/CAN1_TX_25") (pintype "bidirectional+no_connect"))
    )
    (net (code "83") (name "unconnected-(U100-PB13{slash}COM4_1{slash}CAN1_RX-Pad26)") (class "Default")
      (node (ref "U100") (pin "26") (pinfunction "PB13/COM4_1/CAN1_RX_26") (pintype "bidirectional+no_connect"))
    )
    (net (code "84") (name "unconnected-(U100-PB22{slash}COM5_2{slash}COM1_2{slash}XIN1-Pad49)") (class "Default")
      (node (ref "U100") (pin "49") (pinfunction "PB22/COM5_2/COM1_2/XIN1_49") (pintype "bidirectional+no_connect"))
    )
    (net (code "85") (name "unconnected-(U100-PB23{slash}COM5_3{slash}COM1_3{slash}XOUT1-Pad50)") (class "Default")
      (node (ref "U100") (pin "50") (pinfunction "PB23/COM5_3/COM1_3/XOUT1_50") (pintype "bidirectional+no_connect"))
    )
    (net (code "86") (name "unconnected-(U100-PB30{slash}SWO-Pad59)") (class "Default")
      (node (ref "U100") (pin "59") (pinfunction "PB30/SWO_59") (pintype "bidirectional+no_connect"))
    )
    (net (code "87") (name "unconnected-(U100-PB31{slash}COM5_0{slash}COM7_1-Pad60)") (class "Default")
      (node (ref "U100") (pin "60") (pinfunction "PB31/COM5_0/COM7_1_60") (pintype "bidirectional+no_connect"))
    )
    (net (code "88") (name "unconnected-(U100-VSW-Pad55)") (class "Default")
      (node (ref "U100") (pin "55") (pinfunction "VSW_55") (pintype "passive+no_connect"))
    )
    (net (code "89") (name "unconnected-(X102-Pad4)") (class "Default")
      (node (ref "X102") (pin "4") (pinfunction "4_4") (pintype "passive"))
    )
    (net (code "90") (name "unconnected-(X102-Pad5)") (class "Default")
      (node (ref "X102") (pin "5") (pinfunction "5_5") (pintype "passive"))
    )
    (net (code "91") (name "unconnected-(X102-Pad6)") (class "Default")
      (node (ref "X102") (pin "6") (pinfunction "6_6") (pintype "passive"))
    )
    (net (code "92") (name "unconnected-(X102-Pad9)") (class "Default")
      (node (ref "X102") (pin "9") (pinfunction "9_9") (pintype "passive"))
    )
    (net (code "93") (name "unconnected-(X102-PadSH)") (class "Default")
      (node (ref "X102") (pin "SH") (pinfunction "SH_SH") (pintype "passive"))
    )
    (net (code "94") (name "unconnected-(X104-KEY-Pad7)") (class "Default")
      (node (ref "X104") (pin "7") (pinfunction "KEY_7") (pintype "passive"))
    )
    (net (code "95") (name "unconnected-(X104-NC{slash}TDI-Pad8)") (class "Default")
      (node (ref "X104") (pin "8") (pinfunction "NC/TDI_8") (pintype "passive"))
    )
    (net (code "96") (name "unconnected-(X104-SWO{slash}TDO-Pad6)") (class "Default")
      (node (ref "X104") (pin "6") (pinfunction "SWO/TDO_6") (pintype "passive"))
    )
  )
)
